# Teensylu2-0_6.net
KiCad netlist of a schematic drawn in EAGLE
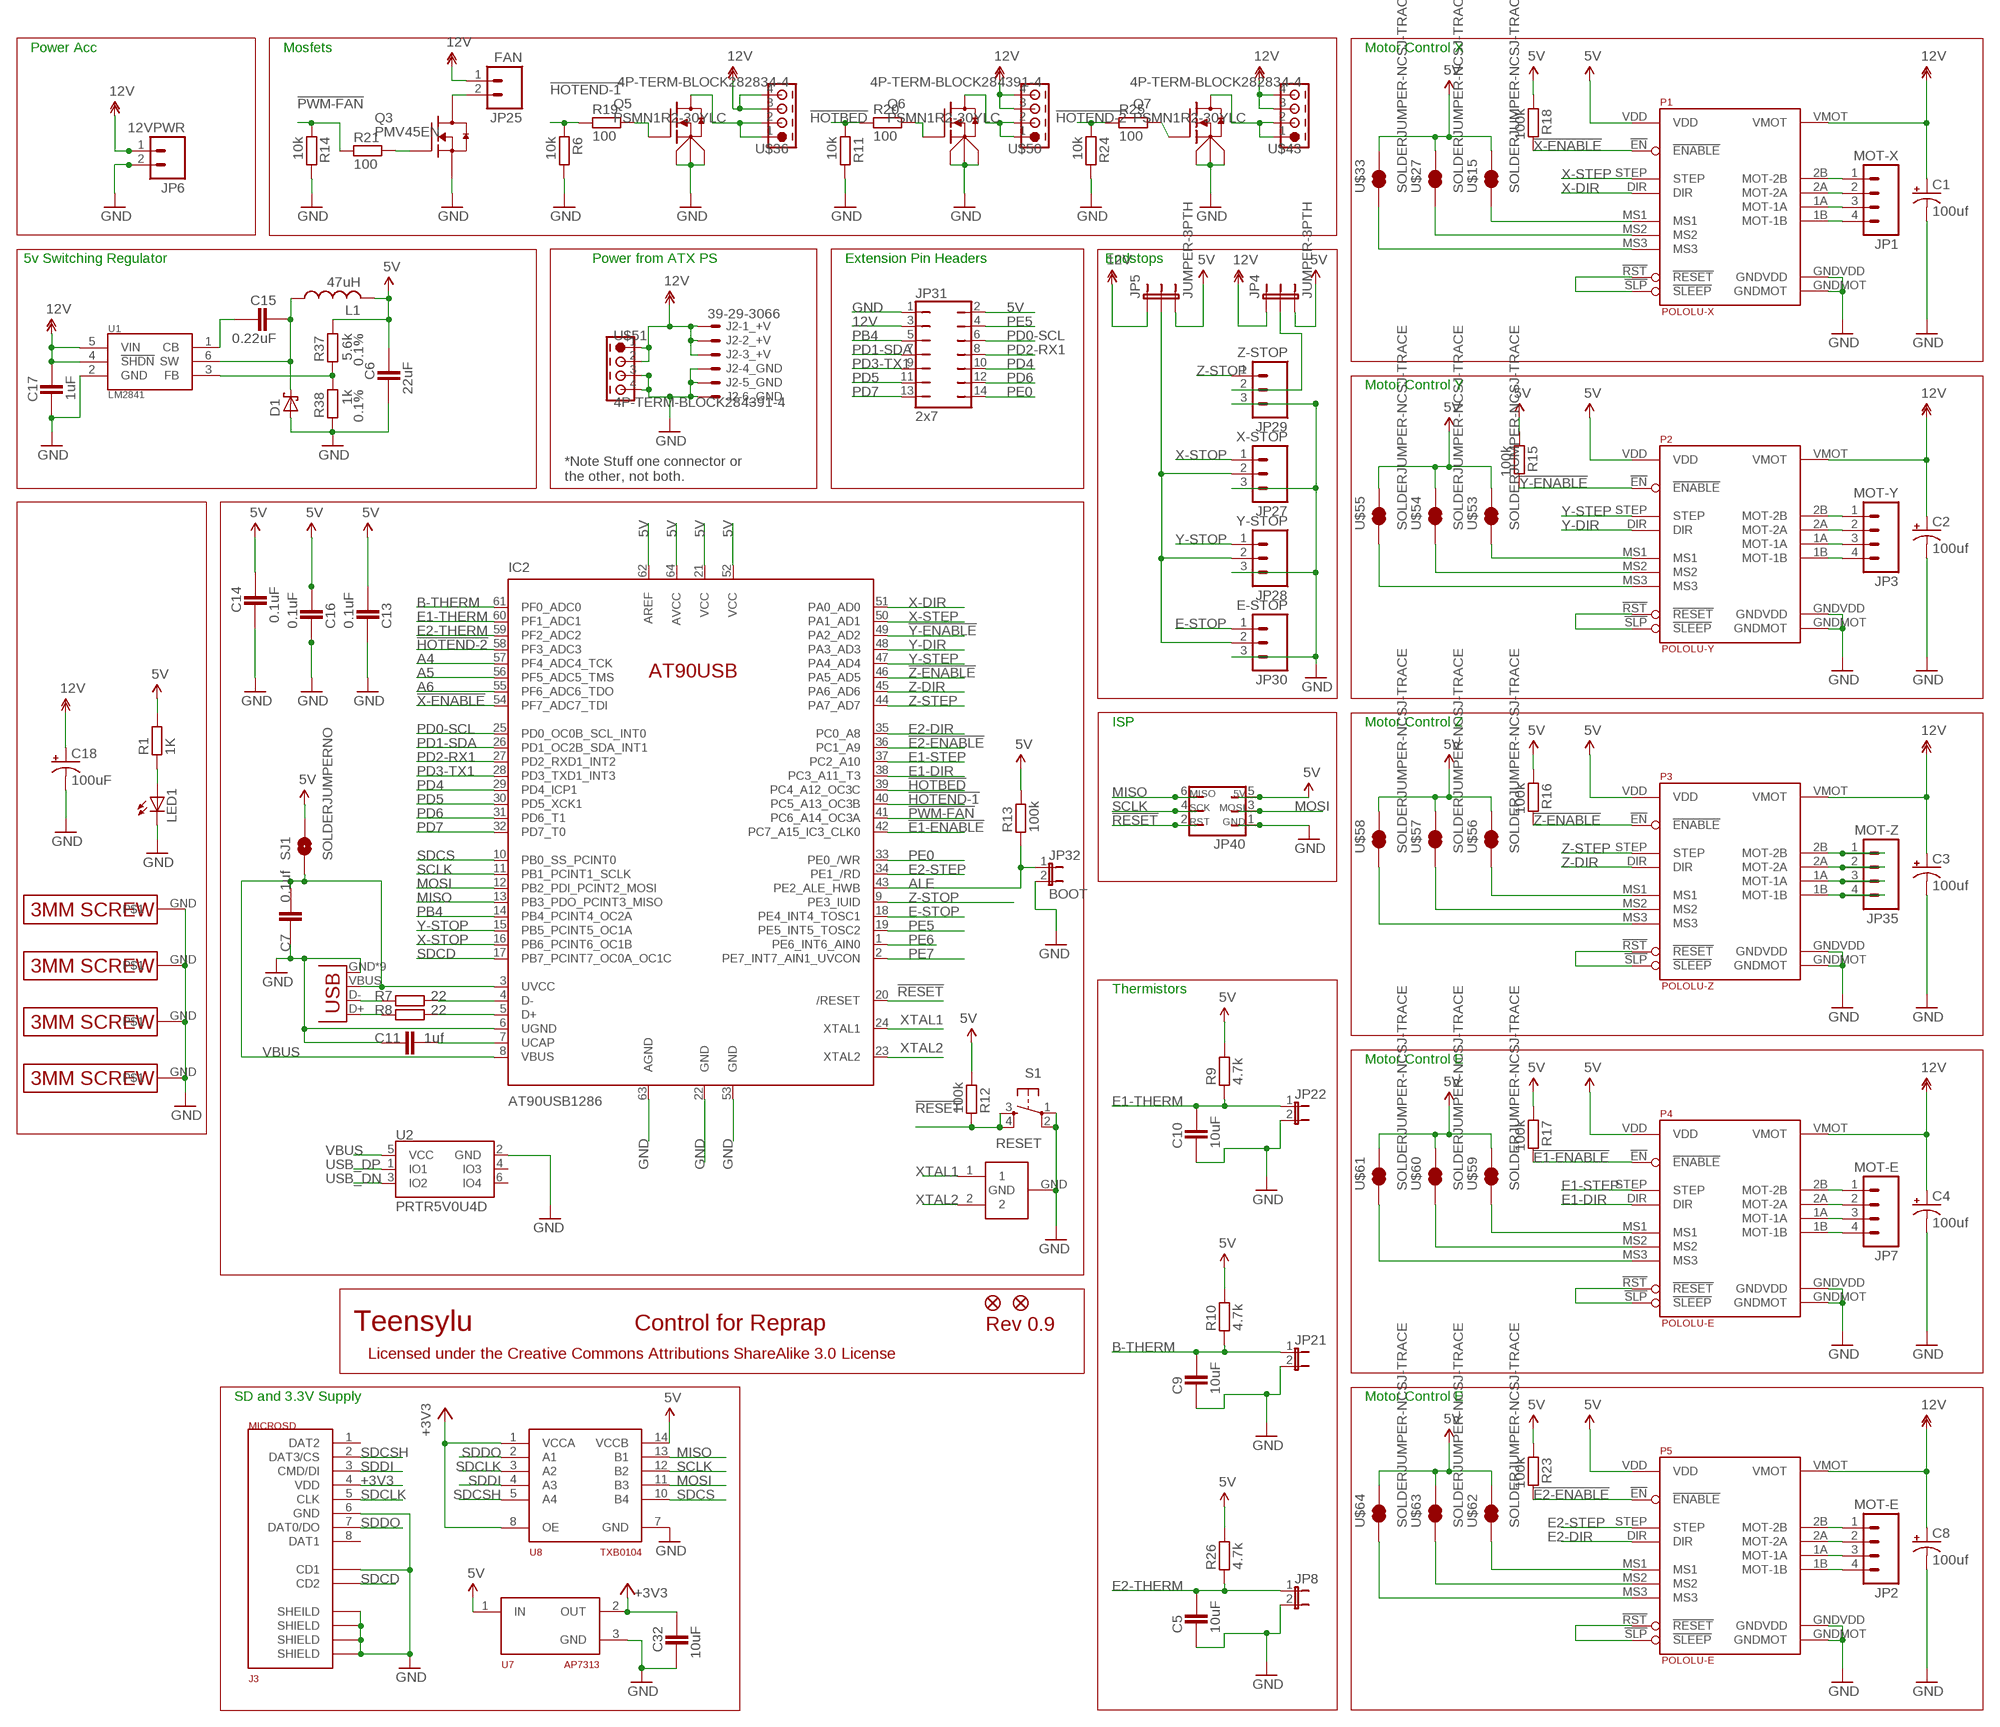
[diagram p0: schematic, sheet 1]

(export (version "E")
  (design (tool "Eeschema 10.0.6"))
  (components
    (comp (ref "C1")
      (value "100uf")
      (footprint "eagle-import:CPOL-RADIAL-100UF-25V")
      (libsource (lib "eagle-import") (part "CAP_POLPTH1"))
    )
    (comp (ref "C2")
      (value "100uf")
      (footprint "eagle-import:CPOL-RADIAL-100UF-25V")
      (libsource (lib "eagle-import") (part "CAP_POLPTH1"))
    )
    (comp (ref "C3")
      (value "100uf")
      (footprint "eagle-import:CPOL-RADIAL-100UF-25V")
      (libsource (lib "eagle-import") (part "CAP_POLPTH1"))
    )
    (comp (ref "C4")
      (value "100uf")
      (footprint "eagle-import:CPOL-RADIAL-100UF-25V")
      (libsource (lib "eagle-import") (part "CAP_POLPTH1"))
    )
    (comp (ref "C5")
      (value "10uF")
      (footprint "eagle-import:CAPC1608X92N")
      (libsource (lib "eagle-import") (part "CAPACITOR_0603"))
    )
    (comp (ref "C6")
      (value "22uF")
      (footprint "eagle-import:CAPC2012X145AN")
      (libsource (lib "eagle-import") (part "CAPACITOR_0805"))
    )
    (comp (ref "C7")
      (value "0.1uf")
      (footprint "eagle-import:CAPC1608X92N")
      (libsource (lib "eagle-import") (part "CAPACITOR_0603"))
    )
    (comp (ref "C8")
      (value "100uf")
      (footprint "eagle-import:CPOL-RADIAL-100UF-25V")
      (libsource (lib "eagle-import") (part "CAP_POLPTH1"))
    )
    (comp (ref "C9")
      (value "10uF")
      (footprint "eagle-import:CAPC1608X92N")
      (libsource (lib "eagle-import") (part "CAPACITOR_0603"))
    )
    (comp (ref "C10")
      (value "10uF")
      (footprint "eagle-import:CAPC1608X92N")
      (libsource (lib "eagle-import") (part "CAPACITOR_0603"))
    )
    (comp (ref "C11")
      (value "1uf")
      (footprint "eagle-import:CAPC1608X92N")
      (libsource (lib "eagle-import") (part "CAPACITOR_0603"))
    )
    (comp (ref "C13")
      (value "0.1uF")
      (footprint "eagle-import:CAPC1608X92N")
      (libsource (lib "eagle-import") (part "CAPACITOR_0603"))
    )
    (comp (ref "C14")
      (value "0.1uF")
      (footprint "eagle-import:CAPC1608X92N")
      (libsource (lib "eagle-import") (part "CAPACITOR_0603"))
    )
    (comp (ref "C15")
      (value "0.22uF")
      (footprint "eagle-import:CAPC1608X92N")
      (libsource (lib "eagle-import") (part "CAPACITOR_0603"))
    )
    (comp (ref "C16")
      (value "0.1uF")
      (footprint "eagle-import:CAPC1608X92N")
      (libsource (lib "eagle-import") (part "CAPACITOR_0603"))
    )
    (comp (ref "C17")
      (value "1uF")
      (footprint "eagle-import:CAPC2012X145AN")
      (libsource (lib "eagle-import") (part "CAPACITOR_0805"))
    )
    (comp (ref "C18")
      (value "100uF")
      (footprint "eagle-import:PANASONIC_D")
      (libsource (lib "eagle-import") (part "CPOL-USD"))
    )
    (comp (ref "C32")
      (value "10uF")
      (footprint "eagle-import:CAPC2012X145AN")
      (libsource (lib "eagle-import") (part "CAPACITOR_0805"))
    )
    (comp (ref "D1")
      (value "SCH-DIODESMA")
      (footprint "eagle-import:SMA")
      (libsource (lib "eagle-import") (part "SCH-DIODESMA"))
    )
    (comp (ref "IC2")
      (value "AT90USB1286")
      (footprint "eagle-import:TQFP64-2")
      (libsource (lib "eagle-import") (part "AT90USB"))
    )
    (comp (ref "J1")
      (value "USB-MICRO-PTH")
      (footprint "eagle-import:USB-MICROB-PTH")
      (libsource (lib "eagle-import") (part "USB-MICRO-PTH"))
    )
    (comp (ref "J2")
      (value "39-29-3066")
      (footprint "eagle-import:39-29-3066")
      (libsource (lib "eagle-import") (part "39-29-3066"))
    )
    (comp (ref "J3")
      (value "MICROSD")
      (footprint "eagle-import:AMPHENOL-MICROSD")
      (libsource (lib "eagle-import") (part "MICROSD"))
    )
    (comp (ref "JP1")
      (value "MOT-X")
      (footprint "eagle-import:MOLEX-1X4")
      (libsource (lib "eagle-import") (part "M04POLAR"))
    )
    (comp (ref "JP2")
      (value "MOT-E")
      (footprint "eagle-import:MOLEX-1X4")
      (libsource (lib "eagle-import") (part "M04POLAR"))
    )
    (comp (ref "JP3")
      (value "MOT-Y")
      (footprint "eagle-import:MOLEX-1X4")
      (libsource (lib "eagle-import") (part "M04POLAR"))
    )
    (comp (ref "JP4")
      (value "JUMPER-3PTH")
      (footprint "eagle-import:1X03")
      (libsource (lib "eagle-import") (part "JUMPER-3PTH"))
    )
    (comp (ref "JP5")
      (value "JUMPER-3PTH")
      (footprint "eagle-import:1X03")
      (libsource (lib "eagle-import") (part "JUMPER-3PTH"))
    )
    (comp (ref "JP6")
      (value "12VPWR")
      (footprint "eagle-import:MOLEX-1X2")
      (libsource (lib "eagle-import") (part "M02POLAR"))
    )
    (comp (ref "JP7")
      (value "MOT-E")
      (footprint "eagle-import:MOLEX-1X4")
      (libsource (lib "eagle-import") (part "M04POLAR"))
    )
    (comp (ref "JP8")
      (value "JUMPER-2PTH")
      (footprint "eagle-import:1X02")
      (libsource (lib "eagle-import") (part "JUMPER-2PTH"))
    )
    (comp (ref "JP21")
      (value "JUMPER-2PTH")
      (footprint "eagle-import:1X02")
      (libsource (lib "eagle-import") (part "JUMPER-2PTH"))
    )
    (comp (ref "JP22")
      (value "JUMPER-2PTH")
      (footprint "eagle-import:1X02")
      (libsource (lib "eagle-import") (part "JUMPER-2PTH"))
    )
    (comp (ref "JP25")
      (value "FAN")
      (footprint "eagle-import:MOLEX-1X2")
      (libsource (lib "eagle-import") (part "M02POLAR"))
    )
    (comp (ref "JP26")
      (value "FIDUCIAL1X2.5")
      (footprint "eagle-import:FIDUCIAL-1X2.5")
      (libsource (lib "eagle-import") (part "FIDUCIAL1X2.5"))
    )
    (comp (ref "JP27")
      (value "X-STOP")
      (footprint "eagle-import:MOLEX-1X3")
      (libsource (lib "eagle-import") (part "M03POLAR"))
    )
    (comp (ref "JP28")
      (value "Y-STOP")
      (footprint "eagle-import:MOLEX-1X3")
      (libsource (lib "eagle-import") (part "M03POLAR"))
    )
    (comp (ref "JP29")
      (value "Z-STOP")
      (footprint "eagle-import:MOLEX-1X3")
      (libsource (lib "eagle-import") (part "M03POLAR"))
    )
    (comp (ref "JP30")
      (value "E-STOP")
      (footprint "eagle-import:MOLEX-1X3")
      (libsource (lib "eagle-import") (part "M03POLAR"))
    )
    (comp (ref "JP31")
      (value "2x7")
      (footprint "eagle-import:JP7Q")
      (libsource (lib "eagle-import") (part "JP7Q"))
    )
    (comp (ref "JP32")
      (value "BOOT")
      (footprint "eagle-import:1X02")
      (libsource (lib "eagle-import") (part "JUMPER-2PTH"))
    )
    (comp (ref "JP33")
      (value "FIDUCIAL1X2.5")
      (footprint "eagle-import:FIDUCIAL-1X2.5")
      (libsource (lib "eagle-import") (part "FIDUCIAL1X2.5"))
    )
    (comp (ref "JP35")
      (value "MOT-Z")
      (footprint "eagle-import:MOLEX-1X4")
      (libsource (lib "eagle-import") (part "M04POLAR"))
    )
    (comp (ref "JP40")
      (value "PROGHEADER")
      (footprint "eagle-import:ISP")
      (libsource (lib "eagle-import") (part "PROGHEADER"))
    )
    (comp (ref "L1")
      (value "47uH")
      (footprint "eagle-import:SDR1006")
      (libsource (lib "eagle-import") (part "L-US"))
    )
    (comp (ref "LED1")
      (value "LEDCHIPLED_0805")
      (footprint "eagle-import:CHIPLED_0805")
      (libsource (lib "eagle-import") (part "LEDCHIPLED_0805"))
    )
    (comp (ref "P1")
      (value "POLOLU-X")
      (footprint "eagle-import:POLOLU-STEPPER-PTH")
      (libsource (lib "eagle-import") (part "POLOLU-ALLEGRO"))
    )
    (comp (ref "P2")
      (value "POLOLU-Y")
      (footprint "eagle-import:POLOLU-STEPPER-PTH")
      (libsource (lib "eagle-import") (part "POLOLU-ALLEGRO"))
    )
    (comp (ref "P3")
      (value "POLOLU-Z")
      (footprint "eagle-import:POLOLU-STEPPER-PTH")
      (libsource (lib "eagle-import") (part "POLOLU-ALLEGRO"))
    )
    (comp (ref "P4")
      (value "POLOLU-E")
      (footprint "eagle-import:POLOLU-STEPPER-PTH")
      (libsource (lib "eagle-import") (part "POLOLU-ALLEGRO"))
    )
    (comp (ref "P5")
      (value "POLOLU-E")
      (footprint "eagle-import:POLOLU-STEPPER-PTH")
      (libsource (lib "eagle-import") (part "POLOLU-ALLEGRO"))
    )
    (comp (ref "Q3")
      (value "PMV45EN")
      (footprint "eagle-import:SOT95P280X135-3N")
      (libsource (lib "eagle-import") (part "MOSFET-NCH_SOT-23"))
    )
    (comp (ref "Q5")
      (value "PSMN1R2-30YLC")
      (footprint "eagle-import:LFPACK-POWERPAK-SO8")
      (libsource (lib "eagle-import") (part "PSMN1R2-30YLC"))
    )
    (comp (ref "Q6")
      (value "PSMN1R2-30YLC")
      (footprint "eagle-import:LFPACK-POWERPAK-SO8")
      (libsource (lib "eagle-import") (part "PSMN1R2-30YLC"))
    )
    (comp (ref "Q7")
      (value "PSMN1R2-30YLC")
      (footprint "eagle-import:LFPACK-POWERPAK-SO8")
      (libsource (lib "eagle-import") (part "PSMN1R2-30YLC"))
    )
    (comp (ref "R1")
      (value "1K")
      (footprint "eagle-import:RESC1608X55N")
      (libsource (lib "eagle-import") (part "RESISTOR_0603"))
    )
    (comp (ref "R6")
      (value "10k")
      (footprint "eagle-import:RESC1608X55N")
      (libsource (lib "eagle-import") (part "RESISTOR_0603"))
    )
    (comp (ref "R7")
      (value "22")
      (footprint "eagle-import:RESC1608X55N")
      (libsource (lib "eagle-import") (part "RESISTOR_0603"))
    )
    (comp (ref "R8")
      (value "22")
      (footprint "eagle-import:RESC1608X55N")
      (libsource (lib "eagle-import") (part "RESISTOR_0603"))
    )
    (comp (ref "R9")
      (value "4.7k")
      (footprint "eagle-import:RESC1608X55N")
      (libsource (lib "eagle-import") (part "RESISTOR_0603"))
    )
    (comp (ref "R10")
      (value "4.7k")
      (footprint "eagle-import:RESC1608X55N")
      (libsource (lib "eagle-import") (part "RESISTOR_0603"))
    )
    (comp (ref "R11")
      (value "10k")
      (footprint "eagle-import:RESC1608X55N")
      (libsource (lib "eagle-import") (part "RESISTOR_0603"))
    )
    (comp (ref "R12")
      (value "100k")
      (footprint "eagle-import:RESC1608X55N")
      (libsource (lib "eagle-import") (part "RESISTOR_0603"))
    )
    (comp (ref "R13")
      (value "100k")
      (footprint "eagle-import:RESC1608X55N")
      (libsource (lib "eagle-import") (part "RESISTOR_0603"))
    )
    (comp (ref "R14")
      (value "10k")
      (footprint "eagle-import:RESC1608X55N")
      (libsource (lib "eagle-import") (part "RESISTOR_0603"))
    )
    (comp (ref "R15")
      (value "100k")
      (footprint "eagle-import:RESC1608X55N")
      (libsource (lib "eagle-import") (part "RESISTOR_0603"))
    )
    (comp (ref "R16")
      (value "100k")
      (footprint "eagle-import:RESC1608X55N")
      (libsource (lib "eagle-import") (part "RESISTOR_0603"))
    )
    (comp (ref "R17")
      (value "100k")
      (footprint "eagle-import:RESC1608X55N")
      (libsource (lib "eagle-import") (part "RESISTOR_0603"))
    )
    (comp (ref "R18")
      (value "100k")
      (footprint "eagle-import:RESC1608X55N")
      (libsource (lib "eagle-import") (part "RESISTOR_0603"))
    )
    (comp (ref "R19")
      (value "100")
      (footprint "eagle-import:RESC1608X55N")
      (libsource (lib "eagle-import") (part "RESISTOR_0603"))
    )
    (comp (ref "R20")
      (value "100")
      (footprint "eagle-import:RESC1608X55N")
      (libsource (lib "eagle-import") (part "RESISTOR_0603"))
    )
    (comp (ref "R21")
      (value "100")
      (footprint "eagle-import:RESC1608X55N")
      (libsource (lib "eagle-import") (part "RESISTOR_0603"))
    )
    (comp (ref "R23")
      (value "100k")
      (footprint "eagle-import:RESC1608X55N")
      (libsource (lib "eagle-import") (part "RESISTOR_0603"))
    )
    (comp (ref "R24")
      (value "10k")
      (footprint "eagle-import:RESC1608X55N")
      (libsource (lib "eagle-import") (part "RESISTOR_0603"))
    )
    (comp (ref "R25")
      (value "100")
      (footprint "eagle-import:RESC1608X55N")
      (libsource (lib "eagle-import") (part "RESISTOR_0603"))
    )
    (comp (ref "R26")
      (value "4.7k")
      (footprint "eagle-import:RESC1608X55N")
      (libsource (lib "eagle-import") (part "RESISTOR_0603"))
    )
    (comp (ref "R37")
      (value "5.6k")
      (footprint "eagle-import:RESC1608X55N")
      (fields (field (name "TOLERANCE") "0.1%"))
      (libsource (lib "eagle-import") (part "RESISTOR_0603"))
    )
    (comp (ref "R38")
      (value "1k")
      (footprint "eagle-import:RESC1608X55N")
      (fields (field (name "TOLERANCE") "0.1%"))
      (libsource (lib "eagle-import") (part "RESISTOR_0603"))
    )
    (comp (ref "S1")
      (value "RESET")
      (footprint "eagle-import:TACTILE-PTH")
      (libsource (lib "eagle-import") (part "TAC_SWITCHPTH"))
    )
    (comp (ref "SJ1")
      (value "SOLDERJUMPERNO")
      (footprint "eagle-import:SJ_2S-NO")
      (libsource (lib "eagle-import") (part "SOLDERJUMPERNO"))
    )
    (comp (ref "U$15")
      (value "SOLDERJUMPER-NCSJ-TRACE")
      (footprint "eagle-import:SJ_2S-TRACE")
      (libsource (lib "eagle-import") (part "SOLDERJUMPER-NCSJ-TRACE"))
    )
    (comp (ref "U$17")
      (value "3MM-SCREW")
      (footprint "eagle-import:PLATEDSCREW")
      (libsource (lib "eagle-import") (part "3MM-SCREW"))
    )
    (comp (ref "U$24")
      (value "3MM-SCREW")
      (footprint "eagle-import:PLATEDSCREW")
      (libsource (lib "eagle-import") (part "3MM-SCREW"))
    )
    (comp (ref "U$27")
      (value "SOLDERJUMPER-NCSJ-TRACE")
      (footprint "eagle-import:SJ_2S-TRACE")
      (libsource (lib "eagle-import") (part "SOLDERJUMPER-NCSJ-TRACE"))
    )
    (comp (ref "U$33")
      (value "SOLDERJUMPER-NCSJ-TRACE")
      (footprint "eagle-import:SJ_2S-TRACE")
      (libsource (lib "eagle-import") (part "SOLDERJUMPER-NCSJ-TRACE"))
    )
    (comp (ref "U$34")
      (value "3MM-SCREW")
      (footprint "eagle-import:PLATEDSCREW")
      (libsource (lib "eagle-import") (part "3MM-SCREW"))
    )
    (comp (ref "U$36")
      (value "4P-TERM-BLOCK282834-4")
      (footprint "eagle-import:282834-4")
      (libsource (lib "eagle-import") (part "4P-TERM-BLOCK282834-4"))
    )
    (comp (ref "U$37")
      (value "3MM-SCREW")
      (footprint "eagle-import:PLATEDSCREW")
      (libsource (lib "eagle-import") (part "3MM-SCREW"))
    )
    (comp (ref "U$43")
      (value "4P-TERM-BLOCK282834-4")
      (footprint "eagle-import:282834-4")
      (libsource (lib "eagle-import") (part "4P-TERM-BLOCK282834-4"))
    )
    (comp (ref "U$50")
      (value "4P-TERM-BLOCK284391-4")
      (footprint "eagle-import:284391-4")
      (libsource (lib "eagle-import") (part "4P-TERM-BLOCK284391-4"))
    )
    (comp (ref "U$51")
      (value "4P-TERM-BLOCK284391-4")
      (footprint "eagle-import:284391-4")
      (libsource (lib "eagle-import") (part "4P-TERM-BLOCK284391-4"))
    )
    (comp (ref "U$53")
      (value "SOLDERJUMPER-NCSJ-TRACE")
      (footprint "eagle-import:SJ_2S-TRACE")
      (libsource (lib "eagle-import") (part "SOLDERJUMPER-NCSJ-TRACE"))
    )
    (comp (ref "U$54")
      (value "SOLDERJUMPER-NCSJ-TRACE")
      (footprint "eagle-import:SJ_2S-TRACE")
      (libsource (lib "eagle-import") (part "SOLDERJUMPER-NCSJ-TRACE"))
    )
    (comp (ref "U$55")
      (value "SOLDERJUMPER-NCSJ-TRACE")
      (footprint "eagle-import:SJ_2S-TRACE")
      (libsource (lib "eagle-import") (part "SOLDERJUMPER-NCSJ-TRACE"))
    )
    (comp (ref "U$56")
      (value "SOLDERJUMPER-NCSJ-TRACE")
      (footprint "eagle-import:SJ_2S-TRACE")
      (libsource (lib "eagle-import") (part "SOLDERJUMPER-NCSJ-TRACE"))
    )
    (comp (ref "U$57")
      (value "SOLDERJUMPER-NCSJ-TRACE")
      (footprint "eagle-import:SJ_2S-TRACE")
      (libsource (lib "eagle-import") (part "SOLDERJUMPER-NCSJ-TRACE"))
    )
    (comp (ref "U$58")
      (value "SOLDERJUMPER-NCSJ-TRACE")
      (footprint "eagle-import:SJ_2S-TRACE")
      (libsource (lib "eagle-import") (part "SOLDERJUMPER-NCSJ-TRACE"))
    )
    (comp (ref "U$59")
      (value "SOLDERJUMPER-NCSJ-TRACE")
      (footprint "eagle-import:SJ_2S-TRACE")
      (libsource (lib "eagle-import") (part "SOLDERJUMPER-NCSJ-TRACE"))
    )
    (comp (ref "U$60")
      (value "SOLDERJUMPER-NCSJ-TRACE")
      (footprint "eagle-import:SJ_2S-TRACE")
      (libsource (lib "eagle-import") (part "SOLDERJUMPER-NCSJ-TRACE"))
    )
    (comp (ref "U$61")
      (value "SOLDERJUMPER-NCSJ-TRACE")
      (footprint "eagle-import:SJ_2S-TRACE")
      (libsource (lib "eagle-import") (part "SOLDERJUMPER-NCSJ-TRACE"))
    )
    (comp (ref "U$62")
      (value "SOLDERJUMPER-NCSJ-TRACE")
      (footprint "eagle-import:SJ_2S-TRACE")
      (libsource (lib "eagle-import") (part "SOLDERJUMPER-NCSJ-TRACE"))
    )
    (comp (ref "U$63")
      (value "SOLDERJUMPER-NCSJ-TRACE")
      (footprint "eagle-import:SJ_2S-TRACE")
      (libsource (lib "eagle-import") (part "SOLDERJUMPER-NCSJ-TRACE"))
    )
    (comp (ref "U$64")
      (value "SOLDERJUMPER-NCSJ-TRACE")
      (footprint "eagle-import:SJ_2S-TRACE")
      (libsource (lib "eagle-import") (part "SOLDERJUMPER-NCSJ-TRACE"))
    )
    (comp (ref "U1")
      (value "LM2841")
      (footprint "eagle-import:TSOT6")
      (libsource (lib "eagle-import") (part "LM2841"))
    )
    (comp (ref "U2")
      (value "PRTR5V0U4D")
      (footprint "eagle-import:SOT23-6")
      (libsource (lib "eagle-import") (part "PRTR5V0U4D"))
    )
    (comp (ref "U7")
      (value "AP7313")
      (footprint "eagle-import:SOT23C")
      (libsource (lib "eagle-import") (part "AP7313"))
    )
    (comp (ref "U8")
      (value "TXB0104")
      (footprint "eagle-import:TSSOP14")
      (libsource (lib "eagle-import") (part "TXB0104"))
    )
    (comp (ref "XTAL")
      (value "KYOCERA_PQRC_TYPE_S_RESONATOR")
      (footprint "eagle-import:AVX_3.2X1.3_RESONATOR")
      (libsource (lib "eagle-import") (part "KYOCERA_PQRC_TYPE_S_RESONATOR"))
    )
  )
  (nets
    (net (code "1") (name "+3V3") (class "Default")
      (node (ref "C32") (pin "1") (pinfunction "1_1") (pintype "passive"))
      (node (ref "J3") (pin "4") (pinfunction "VDD_4") (pintype "power_in"))
      (node (ref "U7") (pin "2") (pinfunction "OUT_2") (pintype "power_in"))
      (node (ref "U8") (pin "1") (pinfunction "VCCA_1") (pintype "power_in"))
      (node (ref "U8") (pin "8") (pinfunction "OE_8") (pintype "input"))
    )
    (net (code "2") (name "/A4") (class "Default")
      (node (ref "IC2") (pin "57") (pinfunction "PF4_ADC4_TCK_57") (pintype "bidirectional"))
    )
    (net (code "3") (name "/A5") (class "Default")
      (node (ref "IC2") (pin "56") (pinfunction "PF5_ADC5_TMS_56") (pintype "bidirectional"))
    )
    (net (code "4") (name "/A6") (class "Default")
      (node (ref "IC2") (pin "55") (pinfunction "PF6_ADC6_TDO_55") (pintype "bidirectional"))
    )
    (net (code "5") (name "/ALE") (class "Default")
      (node (ref "IC2") (pin "43") (pinfunction "PE2_ALE_HWB_43") (pintype "bidirectional"))
      (node (ref "JP32") (pin "1") (pinfunction "1_1") (pintype "passive"))
      (node (ref "R13") (pin "1") (pinfunction "1_1") (pintype "passive"))
    )
    (net (code "6") (name "/B-THERM") (class "Default")
      (node (ref "C9") (pin "2") (pinfunction "2_2") (pintype "passive"))
      (node (ref "IC2") (pin "61") (pinfunction "PF0_ADC0_61") (pintype "bidirectional"))
      (node (ref "JP21") (pin "1") (pinfunction "1_1") (pintype "passive"))
      (node (ref "R10") (pin "1") (pinfunction "1_1") (pintype "passive"))
    )
    (net (code "7") (name "/E-STOP") (class "Default")
      (node (ref "IC2") (pin "18") (pinfunction "PE4_INT4_TOSC1_18") (pintype "bidirectional"))
      (node (ref "JP30") (pin "1") (pinfunction "1_1") (pintype "passive"))
    )
    (net (code "8") (name "/E1-DIR") (class "Default")
      (node (ref "IC2") (pin "38") (pinfunction "PC3_A11_T3_38") (pintype "bidirectional"))
      (node (ref "P4") (pin "DIR") (pinfunction "DIR_DIR") (pintype "bidirectional"))
    )
    (net (code "9") (name "/E1-STEP") (class "Default")
      (node (ref "IC2") (pin "37") (pinfunction "PC2_A10_37") (pintype "bidirectional"))
      (node (ref "P4") (pin "STEP") (pinfunction "STEP_STEP") (pintype "bidirectional"))
    )
    (net (code "10") (name "/E1-THERM") (class "Default")
      (node (ref "C10") (pin "2") (pinfunction "2_2") (pintype "passive"))
      (node (ref "IC2") (pin "60") (pinfunction "PF1_ADC1_60") (pintype "bidirectional"))
      (node (ref "JP22") (pin "1") (pinfunction "1_1") (pintype "passive"))
      (node (ref "R9") (pin "1") (pinfunction "1_1") (pintype "passive"))
    )
    (net (code "11") (name "/E2-DIR") (class "Default")
      (node (ref "IC2") (pin "35") (pinfunction "PC0_A8_35") (pintype "bidirectional"))
      (node (ref "P5") (pin "DIR") (pinfunction "DIR_DIR") (pintype "bidirectional"))
    )
    (net (code "12") (name "/E2-STEP") (class "Default")
      (node (ref "IC2") (pin "34") (pinfunction "PE1_/RD_34") (pintype "bidirectional"))
      (node (ref "P5") (pin "STEP") (pinfunction "STEP_STEP") (pintype "bidirectional"))
    )
    (net (code "13") (name "/E2-THERM") (class "Default")
      (node (ref "C5") (pin "2") (pinfunction "2_2") (pintype "passive"))
      (node (ref "IC2") (pin "59") (pinfunction "PF2_ADC2_59") (pintype "bidirectional"))
      (node (ref "JP8") (pin "1") (pinfunction "1_1") (pintype "passive"))
      (node (ref "R26") (pin "1") (pinfunction "1_1") (pintype "passive"))
    )
    (net (code "14") (name "/MISO") (class "Default")
      (node (ref "IC2") (pin "13") (pinfunction "PB3_PDO_PCINT3_MISO_13") (pintype "bidirectional"))
      (node (ref "JP40") (pin "6") (pinfunction "6_6") (pintype "passive"))
      (node (ref "U8") (pin "13") (pinfunction "B1_13") (pintype "bidirectional"))
    )
    (net (code "15") (name "/MOSI") (class "Default")
      (node (ref "IC2") (pin "12") (pinfunction "PB2_PDI_PCINT2_MOSI_12") (pintype "bidirectional"))
      (node (ref "JP40") (pin "3") (pinfunction "3_3") (pintype "passive"))
      (node (ref "U8") (pin "11") (pinfunction "B3_11") (pintype "bidirectional"))
    )
    (net (code "16") (name "/PB4") (class "Default")
      (node (ref "IC2") (pin "14") (pinfunction "PB4_PCINT4_OC2A_14") (pintype "bidirectional"))
      (node (ref "JP31") (pin "5") (pinfunction "5_5") (pintype "passive"))
    )
    (net (code "17") (name "/PD0-SCL") (class "Default")
      (node (ref "IC2") (pin "25") (pinfunction "PD0_OC0B_SCL_INT0_25") (pintype "bidirectional"))
      (node (ref "JP31") (pin "6") (pinfunction "6_6") (pintype "passive"))
    )
    (net (code "18") (name "/PD1-SDA") (class "Default")
      (node (ref "IC2") (pin "26") (pinfunction "PD1_OC2B_SDA_INT1_26") (pintype "bidirectional"))
      (node (ref "JP31") (pin "7") (pinfunction "7_7") (pintype "passive"))
    )
    (net (code "19") (name "/PD2-RX1") (class "Default")
      (node (ref "IC2") (pin "27") (pinfunction "PD2_RXD1_INT2_27") (pintype "bidirectional"))
      (node (ref "JP31") (pin "8") (pinfunction "8_8") (pintype "passive"))
    )
    (net (code "20") (name "/PD3-TX1") (class "Default")
      (node (ref "IC2") (pin "28") (pinfunction "PD3_TXD1_INT3_28") (pintype "bidirectional"))
      (node (ref "JP31") (pin "9") (pinfunction "9_9") (pintype "passive"))
    )
    (net (code "21") (name "/PD4") (class "Default")
      (node (ref "IC2") (pin "29") (pinfunction "PD4_ICP1_29") (pintype "bidirectional"))
      (node (ref "JP31") (pin "10") (pinfunction "10_10") (pintype "passive"))
    )
    (net (code "22") (name "/PD5") (class "Default")
      (node (ref "IC2") (pin "30") (pinfunction "PD5_XCK1_30") (pintype "bidirectional"))
      (node (ref "JP31") (pin "11") (pinfunction "11_11") (pintype "passive"))
    )
    (net (code "23") (name "/PD6") (class "Default")
      (node (ref "IC2") (pin "31") (pinfunction "PD6_T1_31") (pintype "bidirectional"))
      (node (ref "JP31") (pin "12") (pinfunction "12_12") (pintype "passive"))
    )
    (net (code "24") (name "/PD7") (class "Default")
      (node (ref "IC2") (pin "32") (pinfunction "PD7_T0_32") (pintype "bidirectional"))
      (node (ref "JP31") (pin "13") (pinfunction "13_13") (pintype "passive"))
    )
    (net (code "25") (name "/PE0") (class "Default")
      (node (ref "IC2") (pin "33") (pinfunction "PE0_/WR_33") (pintype "bidirectional"))
      (node (ref "JP31") (pin "14") (pinfunction "14_14") (pintype "passive"))
    )
    (net (code "26") (name "/PE5") (class "Default")
      (node (ref "IC2") (pin "19") (pinfunction "PE5_INT5_TOSC2_19") (pintype "bidirectional"))
      (node (ref "JP31") (pin "4") (pinfunction "4_4") (pintype "passive"))
    )
    (net (code "27") (name "/PE6") (class "Default")
      (node (ref "IC2") (pin "1") (pinfunction "PE6_INT6_AIN0_1") (pintype "bidirectional"))
    )
    (net (code "28") (name "/PE7") (class "Default")
      (node (ref "IC2") (pin "2") (pinfunction "PE7_INT7_AIN1_UVCON_2") (pintype "bidirectional"))
    )
    (net (code "29") (name "/SCLK") (class "Default")
      (node (ref "IC2") (pin "11") (pinfunction "PB1_PCINT1_SCLK_11") (pintype "bidirectional"))
      (node (ref "JP40") (pin "4") (pinfunction "4_4") (pintype "passive"))
      (node (ref "U8") (pin "12") (pinfunction "B2_12") (pintype "bidirectional"))
    )
    (net (code "30") (name "/SDCD") (class "Default")
      (node (ref "IC2") (pin "17") (pinfunction "PB7_PCINT7_OC0A_OC1C_17") (pintype "bidirectional"))
      (node (ref "J3") (pin "CD2") (pinfunction "CD2_CD2") (pintype "bidirectional"))
    )
    (net (code "31") (name "/SDCLK") (class "Default")
      (node (ref "J3") (pin "5") (pinfunction "CLK_5") (pintype "input"))
      (node (ref "U8") (pin "3") (pinfunction "A2_3") (pintype "bidirectional"))
    )
    (net (code "32") (name "/SDCS") (class "Default")
      (node (ref "IC2") (pin "10") (pinfunction "PB0_SS_PCINT0_10") (pintype "bidirectional"))
      (node (ref "U8") (pin "10") (pinfunction "B4_10") (pintype "bidirectional"))
    )
    (net (code "33") (name "/SDCSH") (class "Default")
      (node (ref "J3") (pin "2") (pinfunction "DAT3/CS_2") (pintype "bidirectional"))
      (node (ref "U8") (pin "5") (pinfunction "A4_5") (pintype "bidirectional"))
    )
    (net (code "34") (name "/SDDI") (class "Default")
      (node (ref "J3") (pin "3") (pinfunction "CMD/DI_3") (pintype "input"))
      (node (ref "U8") (pin "4") (pinfunction "A3_4") (pintype "bidirectional"))
    )
    (net (code "35") (name "/SDDO") (class "Default")
      (node (ref "J3") (pin "7") (pinfunction "DAT0/DO_7") (pintype "bidirectional"))
      (node (ref "U8") (pin "2") (pinfunction "A1_2") (pintype "bidirectional"))
    )
    (net (code "36") (name "/USB_DN") (class "Default")
      (node (ref "J1") (pin "D-") (pinfunction "D-_D-") (pintype "bidirectional"))
      (node (ref "R7") (pin "1") (pinfunction "1_1") (pintype "passive"))
      (node (ref "U2") (pin "3") (pinfunction "IO2_3") (pintype "bidirectional"))
    )
    (net (code "37") (name "/USB_DP") (class "Default")
      (node (ref "J1") (pin "D+") (pinfunction "D+_D+") (pintype "bidirectional"))
      (node (ref "R8") (pin "1") (pinfunction "1_1") (pintype "passive"))
      (node (ref "U2") (pin "1") (pinfunction "IO1_1") (pintype "bidirectional"))
    )
    (net (code "38") (name "/VBUS") (class "Default")
      (node (ref "C7") (pin "2") (pinfunction "2_2") (pintype "passive"))
      (node (ref "IC2") (pin "3") (pinfunction "UVCC_3") (pintype "power_in"))
      (node (ref "IC2") (pin "8") (pinfunction "VBUS_8") (pintype "bidirectional"))
      (node (ref "J1") (pin "VBUS") (pinfunction "VBUS_VBUS") (pintype "bidirectional"))
      (node (ref "SJ1") (pin "1") (pinfunction "1_1") (pintype "passive"))
      (node (ref "U2") (pin "5") (pinfunction "VCC_5") (pintype "power_in"))
    )
    (net (code "39") (name "/X-DIR") (class "Default")
      (node (ref "IC2") (pin "51") (pinfunction "PA0_AD0_51") (pintype "bidirectional"))
      (node (ref "P1") (pin "DIR") (pinfunction "DIR_DIR") (pintype "bidirectional"))
    )
    (net (code "40") (name "/X-STEP") (class "Default")
      (node (ref "IC2") (pin "50") (pinfunction "PA1_AD1_50") (pintype "bidirectional"))
      (node (ref "P1") (pin "STEP") (pinfunction "STEP_STEP") (pintype "bidirectional"))
    )
    (net (code "41") (name "/X-STOP") (class "Default")
      (node (ref "IC2") (pin "16") (pinfunction "PB6_PCINT6_OC1B_16") (pintype "bidirectional"))
      (node (ref "JP27") (pin "1") (pinfunction "1_1") (pintype "passive"))
    )
    (net (code "42") (name "/XTAL1") (class "Default")
      (node (ref "IC2") (pin "24") (pinfunction "XTAL1_24") (pintype "passive"))
      (node (ref "XTAL") (pin "1") (pinfunction "1_1") (pintype "bidirectional"))
    )
    (net (code "43") (name "/XTAL2") (class "Default")
      (node (ref "IC2") (pin "23") (pinfunction "XTAL2_23") (pintype "passive"))
      (node (ref "XTAL") (pin "2") (pinfunction "2_2") (pintype "bidirectional"))
    )
    (net (code "44") (name "/Y-DIR") (class "Default")
      (node (ref "IC2") (pin "48") (pinfunction "PA3_AD3_48") (pintype "bidirectional"))
      (node (ref "P2") (pin "DIR") (pinfunction "DIR_DIR") (pintype "bidirectional"))
    )
    (net (code "45") (name "/Y-STEP") (class "Default")
      (node (ref "IC2") (pin "47") (pinfunction "PA4_AD4_47") (pintype "bidirectional"))
      (node (ref "P2") (pin "STEP") (pinfunction "STEP_STEP") (pintype "bidirectional"))
    )
    (net (code "46") (name "/Y-STOP") (class "Default")
      (node (ref "IC2") (pin "15") (pinfunction "PB5_PCINT5_OC1A_15") (pintype "bidirectional"))
      (node (ref "JP28") (pin "1") (pinfunction "1_1") (pintype "passive"))
    )
    (net (code "47") (name "/Z-DIR") (class "Default")
      (node (ref "IC2") (pin "45") (pinfunction "PA6_AD6_45") (pintype "bidirectional"))
      (node (ref "P3") (pin "DIR") (pinfunction "DIR_DIR") (pintype "bidirectional"))
    )
    (net (code "48") (name "/Z-STEP") (class "Default")
      (node (ref "IC2") (pin "44") (pinfunction "PA7_AD7_44") (pintype "bidirectional"))
      (node (ref "P3") (pin "STEP") (pinfunction "STEP_STEP") (pintype "bidirectional"))
    )
    (net (code "49") (name "/Z-STOP") (class "Default")
      (node (ref "IC2") (pin "9") (pinfunction "PE3_IUID_9") (pintype "bidirectional"))
      (node (ref "JP29") (pin "1") (pinfunction "1_1") (pintype "passive"))
    )
    (net (code "50") (name "/~{E1-ENABLE}") (class "Default")
      (node (ref "IC2") (pin "42") (pinfunction "PC7_A15_IC3_CLK0_42") (pintype "bidirectional"))
      (node (ref "P4") (pin "!EN") (pinfunction "~{ENABLE}_!EN") (pintype "input"))
      (node (ref "R17") (pin "2") (pinfunction "2_2") (pintype "passive"))
    )
    (net (code "51") (name "/~{E2-ENABLE}") (class "Default")
      (node (ref "IC2") (pin "36") (pinfunction "PC1_A9_36") (pintype "bidirectional"))
      (node (ref "P5") (pin "!EN") (pinfunction "~{ENABLE}_!EN") (pintype "input"))
      (node (ref "R23") (pin "2") (pinfunction "2_2") (pintype "passive"))
    )
    (net (code "52") (name "/~{HOTBED}") (class "Default")
      (node (ref "IC2") (pin "39") (pinfunction "PC4_A12_OC3C_39") (pintype "bidirectional"))
      (node (ref "R11") (pin "1") (pinfunction "1_1") (pintype "passive"))
      (node (ref "R20") (pin "1") (pinfunction "1_1") (pintype "passive"))
    )
    (net (code "53") (name "/~{HOTEND-1}") (class "Default")
      (node (ref "IC2") (pin "40") (pinfunction "PC5_A13_OC3B_40") (pintype "bidirectional"))
      (node (ref "R19") (pin "1") (pinfunction "1_1") (pintype "passive"))
      (node (ref "R6") (pin "1") (pinfunction "1_1") (pintype "passive"))
    )
    (net (code "54") (name "/~{HOTEND-2}") (class "Default")
      (node (ref "IC2") (pin "58") (pinfunction "PF3_ADC3_58") (pintype "bidirectional"))
      (node (ref "R24") (pin "1") (pinfunction "1_1") (pintype "passive"))
      (node (ref "R25") (pin "1") (pinfunction "1_1") (pintype "passive"))
    )
    (net (code "55") (name "/~{PWM-FAN}") (class "Default")
      (node (ref "IC2") (pin "41") (pinfunction "PC6_A14_OC3A_41") (pintype "bidirectional"))
      (node (ref "R14") (pin "1") (pinfunction "1_1") (pintype "passive"))
      (node (ref "R21") (pin "1") (pinfunction "1_1") (pintype "passive"))
    )
    (net (code "56") (name "/~{RESET}") (class "Default")
      (node (ref "IC2") (pin "20") (pinfunction "/RESET_20") (pintype "bidirectional"))
      (node (ref "JP40") (pin "2") (pinfunction "2_2") (pintype "passive"))
      (node (ref "R12") (pin "1") (pinfunction "1_1") (pintype "passive"))
      (node (ref "S1") (pin "3") (pinfunction "3_3") (pintype "passive"))
      (node (ref "S1") (pin "4") (pinfunction "4_4") (pintype "passive"))
    )
    (net (code "57") (name "/~{X-ENABLE}") (class "Default")
      (node (ref "IC2") (pin "54") (pinfunction "PF7_ADC7_TDI_54") (pintype "bidirectional"))
      (node (ref "P1") (pin "!EN") (pinfunction "~{ENABLE}_!EN") (pintype "input"))
      (node (ref "R18") (pin "2") (pinfunction "2_2") (pintype "passive"))
    )
    (net (code "58") (name "/~{Y-ENABLE}") (class "Default")
      (node (ref "IC2") (pin "49") (pinfunction "PA2_AD2_49") (pintype "bidirectional"))
      (node (ref "P2") (pin "!EN") (pinfunction "~{ENABLE}_!EN") (pintype "input"))
      (node (ref "R15") (pin "2") (pinfunction "2_2") (pintype "passive"))
    )
    (net (code "59") (name "/~{Z-ENABLE}") (class "Default")
      (node (ref "IC2") (pin "46") (pinfunction "PA5_AD5_46") (pintype "bidirectional"))
      (node (ref "P3") (pin "!EN") (pinfunction "~{ENABLE}_!EN") (pintype "input"))
      (node (ref "R16") (pin "2") (pinfunction "2_2") (pintype "passive"))
    )
    (net (code "60") (name "5V") (class "Default")
      (node (ref "C13") (pin "2") (pinfunction "2_2") (pintype "passive"))
      (node (ref "C14") (pin "1") (pinfunction "1_1") (pintype "passive"))
      (node (ref "C16") (pin "2") (pinfunction "2_2") (pintype "passive"))
      (node (ref "C6") (pin "1") (pinfunction "1_1") (pintype "passive"))
      (node (ref "IC2") (pin "21") (pinfunction "VCC_21") (pintype "power_in"))
      (node (ref "IC2") (pin "52") (pinfunction "VCC_52") (pintype "power_in"))
      (node (ref "IC2") (pin "62") (pinfunction "AREF_62") (pintype "power_in"))
      (node (ref "IC2") (pin "64") (pinfunction "AVCC_64") (pintype "power_in"))
      (node (ref "JP31") (pin "2") (pinfunction "2_2") (pintype "passive"))
      (node (ref "JP4") (pin "3") (pinfunction "3_3") (pintype "passive"))
      (node (ref "JP40") (pin "5") (pinfunction "5_5") (pintype "passive"))
      (node (ref "JP5") (pin "3") (pinfunction "3_3") (pintype "passive"))
      (node (ref "L1") (pin "P$2") (pinfunction "2_P$2") (pintype "passive"))
      (node (ref "P1") (pin "VDD") (pinfunction "VDD_VDD") (pintype "power_in"))
      (node (ref "P2") (pin "VDD") (pinfunction "VDD_VDD") (pintype "power_in"))
      (node (ref "P3") (pin "VDD") (pinfunction "VDD_VDD") (pintype "power_in"))
      (node (ref "P4") (pin "VDD") (pinfunction "VDD_VDD") (pintype "power_in"))
      (node (ref "P5") (pin "VDD") (pinfunction "VDD_VDD") (pintype "power_in"))
      (node (ref "R1") (pin "2") (pinfunction "2_2") (pintype "passive"))
      (node (ref "R10") (pin "2") (pinfunction "2_2") (pintype "passive"))
      (node (ref "R12") (pin "2") (pinfunction "2_2") (pintype "passive"))
      (node (ref "R13") (pin "2") (pinfunction "2_2") (pintype "passive"))
      (node (ref "R15") (pin "1") (pinfunction "1_1") (pintype "passive"))
      (node (ref "R16") (pin "1") (pinfunction "1_1") (pintype "passive"))
      (node (ref "R17") (pin "1") (pinfunction "1_1") (pintype "passive"))
      (node (ref "R18") (pin "1") (pinfunction "1_1") (pintype "passive"))
      (node (ref "R23") (pin "1") (pinfunction "1_1") (pintype "passive"))
      (node (ref "R26") (pin "2") (pinfunction "2_2") (pintype "passive"))
      (node (ref "R37") (pin "1") (pinfunction "1_1") (pintype "passive"))
      (node (ref "R9") (pin "2") (pinfunction "2_2") (pintype "passive"))
      (node (ref "SJ1") (pin "2") (pinfunction "2_2") (pintype "passive"))
      (node (ref "U$15") (pin "2") (pinfunction "2_2") (pintype "passive"))
      (node (ref "U$27") (pin "2") (pinfunction "2_2") (pintype "passive"))
      (node (ref "U$33") (pin "2") (pinfunction "2_2") (pintype "passive"))
      (node (ref "U$53") (pin "2") (pinfunction "2_2") (pintype "passive"))
      (node (ref "U$54") (pin "2") (pinfunction "2_2") (pintype "passive"))
      (node (ref "U$55") (pin "2") (pinfunction "2_2") (pintype "passive"))
      (node (ref "U$56") (pin "2") (pinfunction "2_2") (pintype "passive"))
      (node (ref "U$57") (pin "2") (pinfunction "2_2") (pintype "passive"))
      (node (ref "U$58") (pin "2") (pinfunction "2_2") (pintype "passive"))
      (node (ref "U$59") (pin "2") (pinfunction "2_2") (pintype "passive"))
      (node (ref "U$60") (pin "2") (pinfunction "2_2") (pintype "passive"))
      (node (ref "U$61") (pin "2") (pinfunction "2_2") (pintype "passive"))
      (node (ref "U$62") (pin "2") (pinfunction "2_2") (pintype "passive"))
      (node (ref "U$63") (pin "2") (pinfunction "2_2") (pintype "passive"))
      (node (ref "U$64") (pin "2") (pinfunction "2_2") (pintype "passive"))
      (node (ref "U7") (pin "1") (pinfunction "IN_1") (pintype "power_in"))
      (node (ref "U8") (pin "14") (pinfunction "VCCB_14") (pintype "power_in"))
    )
    (net (code "61") (name "12V") (class "Default")
      (node (ref "C1") (pin "1") (pinfunction "+_1") (pintype "passive"))
      (node (ref "C17") (pin "1") (pinfunction "1_1") (pintype "passive"))
      (node (ref "C18") (pin "+") (pinfunction "+_+") (pintype "passive"))
      (node (ref "C2") (pin "1") (pinfunction "+_1") (pintype "passive"))
      (node (ref "C3") (pin "1") (pinfunction "+_1") (pintype "passive"))
      (node (ref "C4") (pin "1") (pinfunction "+_1") (pintype "passive"))
      (node (ref "C8") (pin "1") (pinfunction "+_1") (pintype "passive"))
      (node (ref "J2") (pin "1") (pinfunction "S_1") (pintype "passive"))
      (node (ref "J2") (pin "2") (pinfunction "S_2") (pintype "passive"))
      (node (ref "J2") (pin "3") (pinfunction "S_3") (pintype "passive"))
      (node (ref "JP25") (pin "1") (pinfunction "1_1") (pintype "passive"))
      (node (ref "JP31") (pin "3") (pinfunction "3_3") (pintype "passive"))
      (node (ref "JP4") (pin "1") (pinfunction "1_1") (pintype "passive"))
      (node (ref "JP5") (pin "1") (pinfunction "1_1") (pintype "passive"))
      (node (ref "JP6") (pin "1") (pinfunction "1_1") (pintype "passive"))
      (node (ref "P1") (pin "VMOT") (pinfunction "VMOT_VMOT") (pintype "power_in"))
      (node (ref "P2") (pin "VMOT") (pinfunction "VMOT_VMOT") (pintype "power_in"))
      (node (ref "P3") (pin "VMOT") (pinfunction "VMOT_VMOT") (pintype "power_in"))
      (node (ref "P4") (pin "VMOT") (pinfunction "VMOT_VMOT") (pintype "power_in"))
      (node (ref "P5") (pin "VMOT") (pinfunction "VMOT_VMOT") (pintype "power_in"))
      (node (ref "U$36") (pin "3") (pinfunction "3_3") (pintype "power_in"))
      (node (ref "U$36") (pin "4") (pinfunction "4_4") (pintype "power_in"))
      (node (ref "U$43") (pin "3") (pinfunction "3_3") (pintype "power_in"))
      (node (ref "U$43") (pin "4") (pinfunction "4_4") (pintype "power_in"))
      (node (ref "U$50") (pin "3") (pinfunction "3_3") (pintype "power_in"))
      (node (ref "U$50") (pin "4") (pinfunction "4_4") (pintype "power_in"))
      (node (ref "U$51") (pin "1") (pinfunction "1_1") (pintype "power_in"))
      (node (ref "U$51") (pin "2") (pinfunction "2_2") (pintype "power_in"))
      (node (ref "U1") (pin "4") (pinfunction "~{SHDN}_4") (pintype "input"))
      (node (ref "U1") (pin "5") (pinfunction "VIN_5") (pintype "power_in"))
    )
    (net (code "62") (name "GND") (class "Default")
      (node (ref "C1") (pin "2") (pinfunction "-_2") (pintype "passive"))
      (node (ref "C10") (pin "1") (pinfunction "1_1") (pintype "passive"))
      (node (ref "C11") (pin "1") (pinfunction "1_1") (pintype "passive"))
      (node (ref "C13") (pin "1") (pinfunction "1_1") (pintype "passive"))
      (node (ref "C14") (pin "2") (pinfunction "2_2") (pintype "passive"))
      (node (ref "C16") (pin "1") (pinfunction "1_1") (pintype "passive"))
      (node (ref "C17") (pin "2") (pinfunction "2_2") (pintype "passive"))
      (node (ref "C18") (pin "-") (pinfunction "-_-") (pintype "passive"))
      (node (ref "C2") (pin "2") (pinfunction "-_2") (pintype "passive"))
      (node (ref "C3") (pin "2") (pinfunction "-_2") (pintype "passive"))
      (node (ref "C32") (pin "2") (pinfunction "2_2") (pintype "passive"))
      (node (ref "C4") (pin "2") (pinfunction "-_2") (pintype "passive"))
      (node (ref "C5") (pin "1") (pinfunction "1_1") (pintype "passive"))
      (node (ref "C6") (pin "2") (pinfunction "2_2") (pintype "passive"))
      (node (ref "C7") (pin "1") (pinfunction "1_1") (pintype "passive"))
      (node (ref "C8") (pin "2") (pinfunction "-_2") (pintype "passive"))
      (node (ref "C9") (pin "1") (pinfunction "1_1") (pintype "passive"))
      (node (ref "D1") (pin "A") (pinfunction "A_A") (pintype "passive"))
      (node (ref "IC2") (pin "22") (pinfunction "GND_22") (pintype "power_in"))
      (node (ref "IC2") (pin "53") (pinfunction "GND_53") (pintype "power_in"))
      (node (ref "IC2") (pin "6") (pinfunction "UGND_6") (pintype "power_in"))
      (node (ref "IC2") (pin "63") (pinfunction "AGND_63") (pintype "power_in"))
      (node (ref "J1") (pin "GND") (pinfunction "GND_GND") (pintype "bidirectional"))
      (node (ref "J1") (pin "GND1") (pinfunction "GND_GND1") (pintype "bidirectional"))
      (node (ref "J1") (pin "GND2") (pinfunction "GND_GND2") (pintype "bidirectional"))
      (node (ref "J1") (pin "GND3") (pinfunction "GND_GND3") (pintype "bidirectional"))
      (node (ref "J1") (pin "GND4") (pinfunction "GND_GND4") (pintype "bidirectional"))
      (node (ref "J1") (pin "GND5") (pinfunction "GND_GND5") (pintype "bidirectional"))
      (node (ref "J1") (pin "GND6") (pinfunction "GND_GND6") (pintype "bidirectional"))
      (node (ref "J1") (pin "GND7") (pinfunction "GND_GND7") (pintype "bidirectional"))
      (node (ref "J1") (pin "GND8") (pinfunction "GND_GND8") (pintype "bidirectional"))
      (node (ref "J2") (pin "4") (pinfunction "S_4") (pintype "passive"))
      (node (ref "J2") (pin "5") (pinfunction "S_5") (pintype "passive"))
      (node (ref "J2") (pin "6") (pinfunction "S_6") (pintype "passive"))
      (node (ref "J3") (pin "6") (pinfunction "GND_6") (pintype "power_in"))
      (node (ref "J3") (pin "C1") (pinfunction "SHEILD_C1") (pintype "bidirectional"))
      (node (ref "J3") (pin "C2") (pinfunction "SHIELD_C2") (pintype "bidirectional"))
      (node (ref "J3") (pin "C3") (pinfunction "SHIELD_C3") (pintype "bidirectional"))
      (node (ref "J3") (pin "C4") (pinfunction "SHIELD_C4") (pintype "bidirectional"))
      (node (ref "J3") (pin "CD1") (pinfunction "CD1_CD1") (pintype "bidirectional"))
      (node (ref "JP21") (pin "2") (pinfunction "2_2") (pintype "passive"))
      (node (ref "JP22") (pin "2") (pinfunction "2_2") (pintype "passive"))
      (node (ref "JP27") (pin "3") (pinfunction "3_3") (pintype "passive"))
      (node (ref "JP28") (pin "3") (pinfunction "3_3") (pintype "passive"))
      (node (ref "JP29") (pin "3") (pinfunction "3_3") (pintype "passive"))
      (node (ref "JP30") (pin "3") (pinfunction "3_3") (pintype "passive"))
      (node (ref "JP31") (pin "1") (pinfunction "1_1") (pintype "passive"))
      (node (ref "JP32") (pin "2") (pinfunction "2_2") (pintype "passive"))
      (node (ref "JP40") (pin "1") (pinfunction "1_1") (pintype "passive"))
      (node (ref "JP6") (pin "2") (pinfunction "2_2") (pintype "passive"))
      (node (ref "JP8") (pin "2") (pinfunction "2_2") (pintype "passive"))
      (node (ref "LED1") (pin "C") (pinfunction "C_C") (pintype "passive"))
      (node (ref "P1") (pin "GNDMOT") (pinfunction "GNDMOT_GNDMOT") (pintype "power_in"))
      (node (ref "P1") (pin "GNDVDD") (pinfunction "GNDVDD_GNDVDD") (pintype "power_in"))
      (node (ref "P2") (pin "GNDMOT") (pinfunction "GNDMOT_GNDMOT") (pintype "power_in"))
      (node (ref "P2") (pin "GNDVDD") (pinfunction "GNDVDD_GNDVDD") (pintype "power_in"))
      (node (ref "P3") (pin "GNDMOT") (pinfunction "GNDMOT_GNDMOT") (pintype "power_in"))
      (node (ref "P3") (pin "GNDVDD") (pinfunction "GNDVDD_GNDVDD") (pintype "power_in"))
      (node (ref "P4") (pin "GNDMOT") (pinfunction "GNDMOT_GNDMOT") (pintype "power_in"))
      (node (ref "P4") (pin "GNDVDD") (pinfunction "GNDVDD_GNDVDD") (pintype "power_in"))
      (node (ref "P5") (pin "GNDMOT") (pinfunction "GNDMOT_GNDMOT") (pintype "power_in"))
      (node (ref "P5") (pin "GNDVDD") (pinfunction "GNDVDD_GNDVDD") (pintype "power_in"))
      (node (ref "Q3") (pin "2") (pinfunction "S_2") (pintype "passive"))
      (node (ref "Q5") (pin "1") (pinfunction "S1_1") (pintype "passive"))
      (node (ref "Q5") (pin "2") (pinfunction "S2_2") (pintype "passive"))
      (node (ref "Q5") (pin "3") (pinfunction "S3_3") (pintype "passive"))
      (node (ref "Q6") (pin "1") (pinfunction "S1_1") (pintype "passive"))
      (node (ref "Q6") (pin "2") (pinfunction "S2_2") (pintype "passive"))
      (node (ref "Q6") (pin "3") (pinfunction "S3_3") (pintype "passive"))
      (node (ref "Q7") (pin "1") (pinfunction "S1_1") (pintype "passive"))
      (node (ref "Q7") (pin "2") (pinfunction "S2_2") (pintype "passive"))
      (node (ref "Q7") (pin "3") (pinfunction "S3_3") (pintype "passive"))
      (node (ref "R11") (pin "2") (pinfunction "2_2") (pintype "passive"))
      (node (ref "R14") (pin "2") (pinfunction "2_2") (pintype "passive"))
      (node (ref "R24") (pin "2") (pinfunction "2_2") (pintype "passive"))
      (node (ref "R38") (pin "2") (pinfunction "2_2") (pintype "passive"))
      (node (ref "R6") (pin "2") (pinfunction "2_2") (pintype "passive"))
      (node (ref "S1") (pin "1") (pinfunction "1_1") (pintype "passive"))
      (node (ref "S1") (pin "2") (pinfunction "2_2") (pintype "passive"))
      (node (ref "U$17") (pin "GND") (pinfunction "P$1_GND") (pintype "bidirectional"))
      (node (ref "U$24") (pin "GND") (pinfunction "P$1_GND") (pintype "bidirectional"))
      (node (ref "U$34") (pin "GND") (pinfunction "P$1_GND") (pintype "bidirectional"))
      (node (ref "U$37") (pin "GND") (pinfunction "P$1_GND") (pintype "bidirectional"))
      (node (ref "U$51") (pin "3") (pinfunction "3_3") (pintype "power_in"))
      (node (ref "U$51") (pin "4") (pinfunction "4_4") (pintype "power_in"))
      (node (ref "U1") (pin "2") (pinfunction "GND_2") (pintype "power_in"))
      (node (ref "U2") (pin "2") (pinfunction "GND_2") (pintype "power_in"))
      (node (ref "U7") (pin "3") (pinfunction "GND_3") (pintype "power_in"))
      (node (ref "U8") (pin "7") (pinfunction "GND_7") (pintype "power_in"))
      (node (ref "XTAL") (pin "GND") (pinfunction "GND_GND") (pintype "bidirectional"))
    )
    (net (code "63") (name "Net-(IC2-D+)") (class "Default")
      (node (ref "IC2") (pin "5") (pinfunction "D+_5") (pintype "bidirectional"))
      (node (ref "R8") (pin "2") (pinfunction "2_2") (pintype "passive"))
    )
    (net (code "64") (name "Net-(IC2-D-)") (class "Default")
      (node (ref "IC2") (pin "4") (pinfunction "D-_4") (pintype "bidirectional"))
      (node (ref "R7") (pin "2") (pinfunction "2_2") (pintype "passive"))
    )
    (net (code "65") (name "Net-(IC2-UCAP)") (class "Default")
      (node (ref "C11") (pin "2") (pinfunction "2_2") (pintype "passive"))
      (node (ref "IC2") (pin "7") (pinfunction "UCAP_7") (pintype "power_in"))
    )
    (net (code "66") (name "Net-(JP27-Pad2)") (class "Default")
      (node (ref "JP27") (pin "2") (pinfunction "2_2") (pintype "passive"))
      (node (ref "JP28") (pin "2") (pinfunction "2_2") (pintype "passive"))
      (node (ref "JP30") (pin "2") (pinfunction "2_2") (pintype "passive"))
      (node (ref "JP5") (pin "2") (pinfunction "2_2") (pintype "passive"))
    )
    (net (code "67") (name "Net-(JP29-Pad2)") (class "Default")
      (node (ref "JP29") (pin "2") (pinfunction "2_2") (pintype "passive"))
      (node (ref "JP4") (pin "2") (pinfunction "2_2") (pintype "passive"))
    )
    (net (code "68") (name "Net-(L1-1)") (class "Default")
      (node (ref "C15") (pin "1") (pinfunction "1_1") (pintype "passive"))
      (node (ref "D1") (pin "C") (pinfunction "C_C") (pintype "passive"))
      (node (ref "L1") (pin "P$1") (pinfunction "1_P$1") (pintype "passive"))
      (node (ref "U1") (pin "6") (pinfunction "SW_6") (pintype "passive"))
    )
    (net (code "69") (name "Net-(LED1-PadA)") (class "Default")
      (node (ref "LED1") (pin "A") (pinfunction "A_A") (pintype "passive"))
      (node (ref "R1") (pin "1") (pinfunction "1_1") (pintype "passive"))
    )
    (net (code "70") (name "Net-(P1-MOT-1A)") (class "Default")
      (node (ref "JP1") (pin "3") (pinfunction "3_3") (pintype "passive"))
      (node (ref "P1") (pin "1A") (pinfunction "MOT-1A_1A") (pintype "power_in"))
    )
    (net (code "71") (name "Net-(P1-MOT-1B)") (class "Default")
      (node (ref "JP1") (pin "4") (pinfunction "4_4") (pintype "passive"))
      (node (ref "P1") (pin "1B") (pinfunction "MOT-1B_1B") (pintype "power_in"))
    )
    (net (code "72") (name "Net-(P1-MOT-2A)") (class "Default")
      (node (ref "JP1") (pin "2") (pinfunction "2_2") (pintype "passive"))
      (node (ref "P1") (pin "2A") (pinfunction "MOT-2A_2A") (pintype "power_in"))
    )
    (net (code "73") (name "Net-(P1-MOT-2B)") (class "Default")
      (node (ref "JP1") (pin "1") (pinfunction "1_1") (pintype "passive"))
      (node (ref "P1") (pin "2B") (pinfunction "MOT-2B_2B") (pintype "power_in"))
    )
    (net (code "74") (name "Net-(P1-PadMS1)") (class "Default")
      (node (ref "P1") (pin "MS1") (pinfunction "MS1_MS1") (pintype "input"))
      (node (ref "U$15") (pin "1") (pinfunction "1_1") (pintype "passive"))
    )
    (net (code "75") (name "Net-(P1-PadMS2)") (class "Default")
      (node (ref "P1") (pin "MS2") (pinfunction "MS2_MS2") (pintype "input"))
      (node (ref "U$27") (pin "1") (pinfunction "1_1") (pintype "passive"))
    )
    (net (code "76") (name "Net-(P1-PadMS3)") (class "Default")
      (node (ref "P1") (pin "MS3") (pinfunction "MS3_MS3") (pintype "input"))
      (node (ref "U$33") (pin "1") (pinfunction "1_1") (pintype "passive"))
    )
    (net (code "77") (name "Net-(P1-~{RESET})") (class "Default")
      (node (ref "P1") (pin "!RST") (pinfunction "~{RESET}_!RST") (pintype "input"))
      (node (ref "P1") (pin "!SLP") (pinfunction "~{SLEEP}_!SLP") (pintype "input"))
    )
    (net (code "78") (name "Net-(P2-MOT-1A)") (class "Default")
      (node (ref "JP3") (pin "3") (pinfunction "3_3") (pintype "passive"))
      (node (ref "P2") (pin "1A") (pinfunction "MOT-1A_1A") (pintype "power_in"))
    )
    (net (code "79") (name "Net-(P2-MOT-1B)") (class "Default")
      (node (ref "JP3") (pin "4") (pinfunction "4_4") (pintype "passive"))
      (node (ref "P2") (pin "1B") (pinfunction "MOT-1B_1B") (pintype "power_in"))
    )
    (net (code "80") (name "Net-(P2-MOT-2A)") (class "Default")
      (node (ref "JP3") (pin "2") (pinfunction "2_2") (pintype "passive"))
      (node (ref "P2") (pin "2A") (pinfunction "MOT-2A_2A") (pintype "power_in"))
    )
    (net (code "81") (name "Net-(P2-MOT-2B)") (class "Default")
      (node (ref "JP3") (pin "1") (pinfunction "1_1") (pintype "passive"))
      (node (ref "P2") (pin "2B") (pinfunction "MOT-2B_2B") (pintype "power_in"))
    )
    (net (code "82") (name "Net-(P2-PadMS1)") (class "Default")
      (node (ref "P2") (pin "MS1") (pinfunction "MS1_MS1") (pintype "input"))
      (node (ref "U$53") (pin "1") (pinfunction "1_1") (pintype "passive"))
    )
    (net (code "83") (name "Net-(P2-PadMS2)") (class "Default")
      (node (ref "P2") (pin "MS2") (pinfunction "MS2_MS2") (pintype "input"))
      (node (ref "U$54") (pin "1") (pinfunction "1_1") (pintype "passive"))
    )
    (net (code "84") (name "Net-(P2-PadMS3)") (class "Default")
      (node (ref "P2") (pin "MS3") (pinfunction "MS3_MS3") (pintype "input"))
      (node (ref "U$55") (pin "1") (pinfunction "1_1") (pintype "passive"))
    )
    (net (code "85") (name "Net-(P2-~{RESET})") (class "Default")
      (node (ref "P2") (pin "!RST") (pinfunction "~{RESET}_!RST") (pintype "input"))
      (node (ref "P2") (pin "!SLP") (pinfunction "~{SLEEP}_!SLP") (pintype "input"))
    )
    (net (code "86") (name "Net-(P3-MOT-1A)") (class "Default")
      (node (ref "JP35") (pin "3") (pinfunction "3_3") (pintype "passive"))
      (node (ref "P3") (pin "1A") (pinfunction "MOT-1A_1A") (pintype "power_in"))
    )
    (net (code "87") (name "Net-(P3-MOT-1B)") (class "Default")
      (node (ref "JP35") (pin "4") (pinfunction "4_4") (pintype "passive"))
      (node (ref "P3") (pin "1B") (pinfunction "MOT-1B_1B") (pintype "power_in"))
    )
    (net (code "88") (name "Net-(P3-MOT-2A)") (class "Default")
      (node (ref "JP35") (pin "2") (pinfunction "2_2") (pintype "passive"))
      (node (ref "P3") (pin "2A") (pinfunction "MOT-2A_2A") (pintype "power_in"))
    )
    (net (code "89") (name "Net-(P3-MOT-2B)") (class "Default")
      (node (ref "JP35") (pin "1") (pinfunction "1_1") (pintype "passive"))
      (node (ref "P3") (pin "2B") (pinfunction "MOT-2B_2B") (pintype "power_in"))
    )
    (net (code "90") (name "Net-(P3-PadMS1)") (class "Default")
      (node (ref "P3") (pin "MS1") (pinfunction "MS1_MS1") (pintype "input"))
      (node (ref "U$56") (pin "1") (pinfunction "1_1") (pintype "passive"))
    )
    (net (code "91") (name "Net-(P3-PadMS2)") (class "Default")
      (node (ref "P3") (pin "MS2") (pinfunction "MS2_MS2") (pintype "input"))
      (node (ref "U$57") (pin "1") (pinfunction "1_1") (pintype "passive"))
    )
    (net (code "92") (name "Net-(P3-PadMS3)") (class "Default")
      (node (ref "P3") (pin "MS3") (pinfunction "MS3_MS3") (pintype "input"))
      (node (ref "U$58") (pin "1") (pinfunction "1_1") (pintype "passive"))
    )
    (net (code "93") (name "Net-(P3-~{RESET})") (class "Default")
      (node (ref "P3") (pin "!RST") (pinfunction "~{RESET}_!RST") (pintype "input"))
      (node (ref "P3") (pin "!SLP") (pinfunction "~{SLEEP}_!SLP") (pintype "input"))
    )
    (net (code "94") (name "Net-(P4-MOT-1A)") (class "Default")
      (node (ref "JP7") (pin "3") (pinfunction "3_3") (pintype "passive"))
      (node (ref "P4") (pin "1A") (pinfunction "MOT-1A_1A") (pintype "power_in"))
    )
    (net (code "95") (name "Net-(P4-MOT-1B)") (class "Default")
      (node (ref "JP7") (pin "4") (pinfunction "4_4") (pintype "passive"))
      (node (ref "P4") (pin "1B") (pinfunction "MOT-1B_1B") (pintype "power_in"))
    )
    (net (code "96") (name "Net-(P4-MOT-2A)") (class "Default")
      (node (ref "JP7") (pin "2") (pinfunction "2_2") (pintype "passive"))
      (node (ref "P4") (pin "2A") (pinfunction "MOT-2A_2A") (pintype "power_in"))
    )
    (net (code "97") (name "Net-(P4-MOT-2B)") (class "Default")
      (node (ref "JP7") (pin "1") (pinfunction "1_1") (pintype "passive"))
      (node (ref "P4") (pin "2B") (pinfunction "MOT-2B_2B") (pintype "power_in"))
    )
    (net (code "98") (name "Net-(P4-PadMS1)") (class "Default")
      (node (ref "P4") (pin "MS1") (pinfunction "MS1_MS1") (pintype "input"))
      (node (ref "U$59") (pin "1") (pinfunction "1_1") (pintype "passive"))
    )
    (net (code "99") (name "Net-(P4-PadMS2)") (class "Default")
      (node (ref "P4") (pin "MS2") (pinfunction "MS2_MS2") (pintype "input"))
      (node (ref "U$60") (pin "1") (pinfunction "1_1") (pintype "passive"))
    )
    (net (code "100") (name "Net-(P4-PadMS3)") (class "Default")
      (node (ref "P4") (pin "MS3") (pinfunction "MS3_MS3") (pintype "input"))
      (node (ref "U$61") (pin "1") (pinfunction "1_1") (pintype "passive"))
    )
    (net (code "101") (name "Net-(P4-~{RESET})") (class "Default")
      (node (ref "P4") (pin "!RST") (pinfunction "~{RESET}_!RST") (pintype "input"))
      (node (ref "P4") (pin "!SLP") (pinfunction "~{SLEEP}_!SLP") (pintype "input"))
    )
    (net (code "102") (name "Net-(P5-MOT-1A)") (class "Default")
      (node (ref "JP2") (pin "3") (pinfunction "3_3") (pintype "passive"))
      (node (ref "P5") (pin "1A") (pinfunction "MOT-1A_1A") (pintype "power_in"))
    )
    (net (code "103") (name "Net-(P5-MOT-1B)") (class "Default")
      (node (ref "JP2") (pin "4") (pinfunction "4_4") (pintype "passive"))
      (node (ref "P5") (pin "1B") (pinfunction "MOT-1B_1B") (pintype "power_in"))
    )
    (net (code "104") (name "Net-(P5-MOT-2A)") (class "Default")
      (node (ref "JP2") (pin "2") (pinfunction "2_2") (pintype "passive"))
      (node (ref "P5") (pin "2A") (pinfunction "MOT-2A_2A") (pintype "power_in"))
    )
    (net (code "105") (name "Net-(P5-MOT-2B)") (class "Default")
      (node (ref "JP2") (pin "1") (pinfunction "1_1") (pintype "passive"))
      (node (ref "P5") (pin "2B") (pinfunction "MOT-2B_2B") (pintype "power_in"))
    )
    (net (code "106") (name "Net-(P5-PadMS1)") (class "Default")
      (node (ref "P5") (pin "MS1") (pinfunction "MS1_MS1") (pintype "input"))
      (node (ref "U$62") (pin "1") (pinfunction "1_1") (pintype "passive"))
    )
    (net (code "107") (name "Net-(P5-PadMS2)") (class "Default")
      (node (ref "P5") (pin "MS2") (pinfunction "MS2_MS2") (pintype "input"))
      (node (ref "U$63") (pin "1") (pinfunction "1_1") (pintype "passive"))
    )
    (net (code "108") (name "Net-(P5-PadMS3)") (class "Default")
      (node (ref "P5") (pin "MS3") (pinfunction "MS3_MS3") (pintype "input"))
      (node (ref "U$64") (pin "1") (pinfunction "1_1") (pintype "passive"))
    )
    (net (code "109") (name "Net-(P5-~{RESET})") (class "Default")
      (node (ref "P5") (pin "!RST") (pinfunction "~{RESET}_!RST") (pintype "input"))
      (node (ref "P5") (pin "!SLP") (pinfunction "~{SLEEP}_!SLP") (pintype "input"))
    )
    (net (code "110") (name "Net-(Q3-D)") (class "Default")
      (node (ref "JP25") (pin "2") (pinfunction "2_2") (pintype "passive"))
      (node (ref "Q3") (pin "3") (pinfunction "D_3") (pintype "passive"))
    )
    (net (code "111") (name "Net-(Q3-G)") (class "Default")
      (node (ref "Q3") (pin "1") (pinfunction "G_1") (pintype "passive"))
      (node (ref "R21") (pin "2") (pinfunction "2_2") (pintype "passive"))
    )
    (net (code "112") (name "Net-(Q5-D)") (class "Default")
      (node (ref "Q5") (pin "5-8") (pinfunction "D_5-8") (pintype "passive"))
      (node (ref "U$36") (pin "1") (pinfunction "1_1") (pintype "power_in"))
      (node (ref "U$36") (pin "2") (pinfunction "2_2") (pintype "power_in"))
    )
    (net (code "113") (name "Net-(Q5-G)") (class "Default")
      (node (ref "Q5") (pin "4") (pinfunction "G_4") (pintype "passive"))
      (node (ref "R19") (pin "2") (pinfunction "2_2") (pintype "passive"))
    )
    (net (code "114") (name "Net-(Q6-D)") (class "Default")
      (node (ref "Q6") (pin "5-8") (pinfunction "D_5-8") (pintype "passive"))
      (node (ref "U$50") (pin "1") (pinfunction "1_1") (pintype "power_in"))
      (node (ref "U$50") (pin "2") (pinfunction "2_2") (pintype "power_in"))
    )
    (net (code "115") (name "Net-(Q6-G)") (class "Default")
      (node (ref "Q6") (pin "4") (pinfunction "G_4") (pintype "passive"))
      (node (ref "R20") (pin "2") (pinfunction "2_2") (pintype "passive"))
    )
    (net (code "116") (name "Net-(Q7-D)") (class "Default")
      (node (ref "Q7") (pin "5-8") (pinfunction "D_5-8") (pintype "passive"))
      (node (ref "U$43") (pin "1") (pinfunction "1_1") (pintype "power_in"))
      (node (ref "U$43") (pin "2") (pinfunction "2_2") (pintype "power_in"))
    )
    (net (code "117") (name "Net-(Q7-G)") (class "Default")
      (node (ref "Q7") (pin "4") (pinfunction "G_4") (pintype "passive"))
      (node (ref "R25") (pin "2") (pinfunction "2_2") (pintype "passive"))
    )
    (net (code "118") (name "Net-(U1-CB)") (class "Default")
      (node (ref "C15") (pin "2") (pinfunction "2_2") (pintype "passive"))
      (node (ref "U1") (pin "1") (pinfunction "CB_1") (pintype "passive"))
    )
    (net (code "119") (name "Net-(U1-FB)") (class "Default")
      (node (ref "R37") (pin "2") (pinfunction "2_2") (pintype "passive"))
      (node (ref "R38") (pin "1") (pinfunction "1_1") (pintype "passive"))
      (node (ref "U1") (pin "3") (pinfunction "FB_3") (pintype "passive"))
    )
    (net (code "120") (name "unconnected-(J3-DAT1-Pad8)") (class "Default")
      (node (ref "J3") (pin "8") (pinfunction "DAT1_8") (pintype "bidirectional"))
    )
    (net (code "121") (name "unconnected-(J3-DAT2-Pad1)") (class "Default")
      (node (ref "J3") (pin "1") (pinfunction "DAT2_1") (pintype "bidirectional"))
    )
    (net (code "122") (name "unconnected-(U2-IO3-Pad4)") (class "Default")
      (node (ref "U2") (pin "4") (pinfunction "IO3_4") (pintype "bidirectional"))
    )
    (net (code "123") (name "unconnected-(U2-IO4-Pad6)") (class "Default")
      (node (ref "U2") (pin "6") (pinfunction "IO4_6") (pintype "bidirectional"))
    )
  )
)
